# master.net
KiCad netlist of a schematic drawn in EAGLE
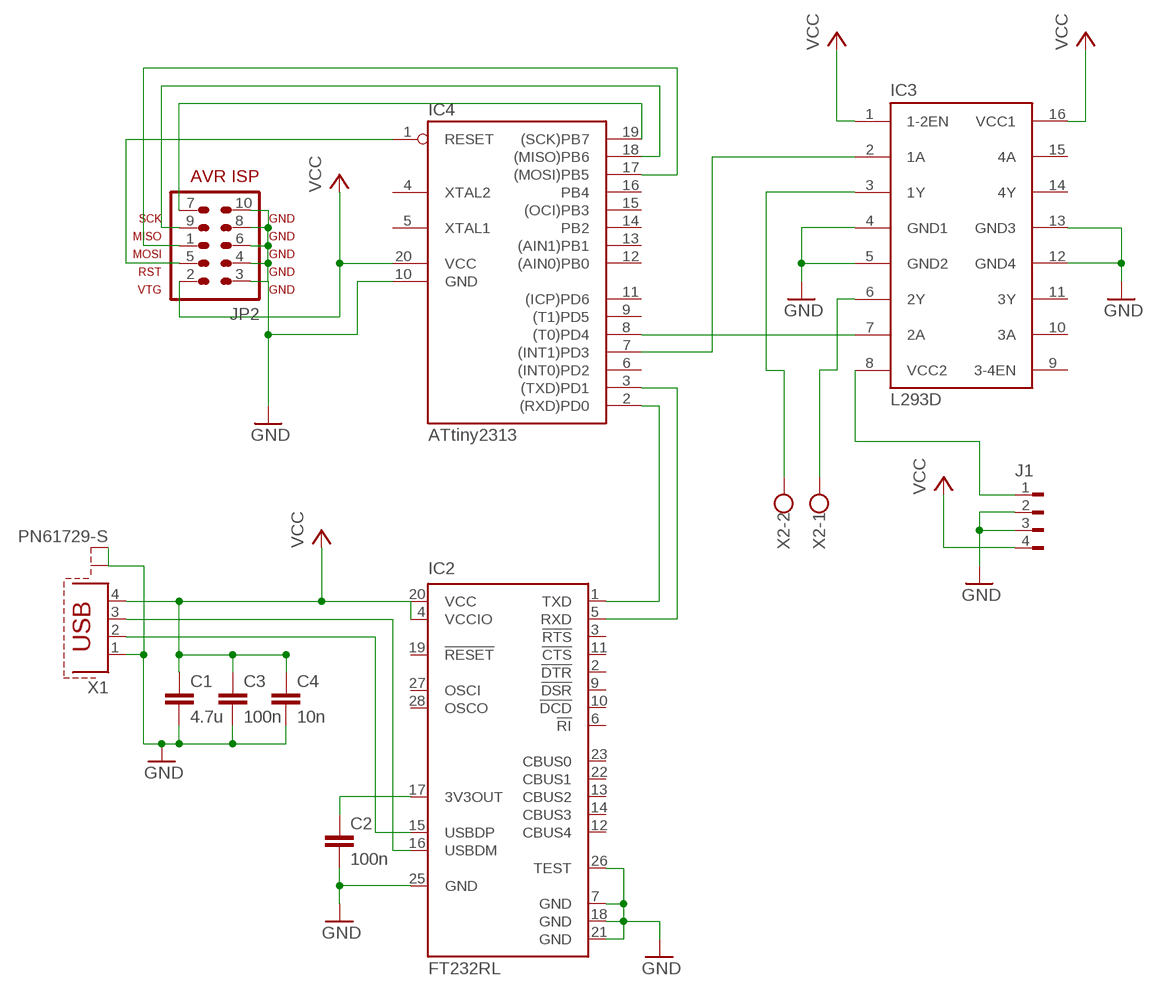
[diagram p0: schematic, sheet 1]

(export (version "E")
  (design (tool "Eeschema 10.0.6"))
  (components
    (comp (ref "C1")
      (value "4.7u")
      (footprint "eagle-import:C025-025X050")
      (libsource (lib "eagle-import") (part "C-EU025-025X050"))
    )
    (comp (ref "C2")
      (value "100n")
      (footprint "eagle-import:C025-025X050")
      (libsource (lib "eagle-import") (part "C-EU025-025X050"))
    )
    (comp (ref "C3")
      (value "100n")
      (footprint "eagle-import:C025-025X050")
      (libsource (lib "eagle-import") (part "C-EU025-025X050"))
    )
    (comp (ref "C4")
      (value "10n")
      (footprint "eagle-import:C025-025X050")
      (libsource (lib "eagle-import") (part "C-EU025-025X050"))
    )
    (comp (ref "IC2")
      (value "FT232RL")
      (footprint "eagle-import:SSOP28")
      (libsource (lib "eagle-import") (part "FT232RL"))
    )
    (comp (ref "IC3")
      (value "L293D")
      (footprint "eagle-import:DIL16")
      (libsource (lib "eagle-import") (part "L293D"))
    )
    (comp (ref "IC4")
      (value "ATtiny2313")
      (footprint "eagle-import:SO20L")
      (libsource (lib "eagle-import") (part "AT90S2313S"))
    )
    (comp (ref "J1")
      (value "FLOPPY-4")
      (footprint "eagle-import:FLOPPY-4")
      (libsource (lib "eagle-import") (part "FLOPPY-4"))
    )
    (comp (ref "JP2")
      (value "AVR-ISP-10")
      (footprint "eagle-import:AVR-ISP-10")
      (libsource (lib "eagle-import") (part "AVR-ISP-10"))
    )
    (comp (ref "X1")
      (value "PN61729-S")
      (footprint "eagle-import:PN61729-S")
      (libsource (lib "eagle-import") (part "PN61729-S"))
    )
    (comp (ref "X2")
      (value "W237-102")
      (footprint "eagle-import:W237-102")
      (fields (field (name "MPN") "237-102"))
      (libsource (lib "eagle-import") (part "W237-102"))
    )
  )
  (nets
    (net (code "1") (name "GND") (class "Default")
      (node (ref "C1") (pin "2") (pinfunction "2_2") (pintype "passive"))
      (node (ref "C2") (pin "2") (pinfunction "2_2") (pintype "passive"))
      (node (ref "C3") (pin "2") (pinfunction "2_2") (pintype "passive"))
      (node (ref "C4") (pin "2") (pinfunction "2_2") (pintype "passive"))
      (node (ref "IC2") (pin "18") (pinfunction "GND_18") (pintype "power_in"))
      (node (ref "IC2") (pin "21") (pinfunction "GND_21") (pintype "power_in"))
      (node (ref "IC2") (pin "25") (pinfunction "GND_25") (pintype "power_in"))
      (node (ref "IC2") (pin "26") (pinfunction "TEST_26") (pintype "input"))
      (node (ref "IC2") (pin "7") (pinfunction "GND_7") (pintype "power_in"))
      (node (ref "IC3") (pin "12") (pinfunction "GND4_12") (pintype "power_in"))
      (node (ref "IC3") (pin "13") (pinfunction "GND3_13") (pintype "power_in"))
      (node (ref "IC3") (pin "4") (pinfunction "GND1_4") (pintype "power_in"))
      (node (ref "IC3") (pin "5") (pinfunction "GND2_5") (pintype "power_in"))
      (node (ref "IC4") (pin "10") (pinfunction "GND_10") (pintype "power_in"))
      (node (ref "J1") (pin "2") (pinfunction "2_2") (pintype "passive"))
      (node (ref "J1") (pin "3") (pinfunction "3_3") (pintype "passive"))
      (node (ref "JP2") (pin "10") (pinfunction "10_10") (pintype "passive"))
      (node (ref "JP2") (pin "3") (pinfunction "3_3") (pintype "passive"))
      (node (ref "JP2") (pin "4") (pinfunction "4_4") (pintype "passive"))
      (node (ref "JP2") (pin "6") (pinfunction "6_6") (pintype "passive"))
      (node (ref "JP2") (pin "8") (pinfunction "8_8") (pintype "passive"))
      (node (ref "X1") (pin "1") (pinfunction "1_1") (pintype "passive"))
      (node (ref "X1") (pin "S1") (pinfunction "S1_S1") (pintype "passive"))
      (node (ref "X1") (pin "S2") (pinfunction "S2_S2") (pintype "passive"))
    )
    (net (code "2") (name "Net-(IC2-3V3OUT)") (class "Default")
      (node (ref "C2") (pin "1") (pinfunction "1_1") (pintype "passive"))
      (node (ref "IC2") (pin "17") (pinfunction "3V3OUT_17") (pintype "output"))
    )
    (net (code "3") (name "Net-(IC2-RXD)") (class "Default")
      (node (ref "IC2") (pin "5") (pinfunction "RXD_5") (pintype "input"))
      (node (ref "IC4") (pin "3") (pinfunction "(TXD)PD1_3") (pintype "bidirectional"))
    )
    (net (code "4") (name "Net-(IC2-TXD)") (class "Default")
      (node (ref "IC2") (pin "1") (pinfunction "TXD_1") (pintype "output"))
      (node (ref "IC4") (pin "2") (pinfunction "(RXD)PD0_2") (pintype "bidirectional"))
    )
    (net (code "5") (name "Net-(IC2-USBDM)") (class "Default")
      (node (ref "IC2") (pin "16") (pinfunction "USBDM_16") (pintype "bidirectional"))
      (node (ref "X1") (pin "3") (pinfunction "3_3") (pintype "passive"))
    )
    (net (code "6") (name "Net-(IC2-USBDP)") (class "Default")
      (node (ref "IC2") (pin "15") (pinfunction "USBDP_15") (pintype "bidirectional"))
      (node (ref "X1") (pin "2") (pinfunction "2_2") (pintype "passive"))
    )
    (net (code "7") (name "Net-(IC3-1A)") (class "Default")
      (node (ref "IC3") (pin "2") (pinfunction "1A_2") (pintype "input"))
      (node (ref "IC4") (pin "7") (pinfunction "(INT1)PD3_7") (pintype "bidirectional"))
    )
    (net (code "8") (name "Net-(IC3-1Y)") (class "Default")
      (node (ref "IC3") (pin "3") (pinfunction "1Y_3") (pintype "output"))
      (node (ref "X2") (pin "2") (pinfunction "KL_2") (pintype "passive"))
    )
    (net (code "9") (name "Net-(IC3-2A)") (class "Default")
      (node (ref "IC3") (pin "7") (pinfunction "2A_7") (pintype "input"))
      (node (ref "IC4") (pin "8") (pinfunction "(T0)PD4_8") (pintype "bidirectional"))
    )
    (net (code "10") (name "Net-(IC3-2Y)") (class "Default")
      (node (ref "IC3") (pin "6") (pinfunction "2Y_6") (pintype "output"))
      (node (ref "X2") (pin "1") (pinfunction "KL_1") (pintype "passive"))
    )
    (net (code "11") (name "Net-(IC3-VCC2)") (class "Default")
      (node (ref "IC3") (pin "8") (pinfunction "VCC2_8") (pintype "power_in"))
      (node (ref "J1") (pin "1") (pinfunction "1_1") (pintype "passive"))
    )
    (net (code "12") (name "Net-(IC4-(MISO)PB6)") (class "Default")
      (node (ref "IC4") (pin "18") (pinfunction "(MISO)PB6_18") (pintype "bidirectional"))
      (node (ref "JP2") (pin "9") (pinfunction "9_9") (pintype "passive"))
    )
    (net (code "13") (name "Net-(IC4-(MOSI)PB5)") (class "Default")
      (node (ref "IC4") (pin "17") (pinfunction "(MOSI)PB5_17") (pintype "bidirectional"))
      (node (ref "JP2") (pin "1") (pinfunction "1_1") (pintype "passive"))
    )
    (net (code "14") (name "Net-(IC4-(SCK)PB7)") (class "Default")
      (node (ref "IC4") (pin "19") (pinfunction "(SCK)PB7_19") (pintype "bidirectional"))
      (node (ref "JP2") (pin "7") (pinfunction "7_7") (pintype "passive"))
    )
    (net (code "15") (name "Net-(IC4-RESET)") (class "Default")
      (node (ref "IC4") (pin "1") (pinfunction "RESET_1") (pintype "bidirectional"))
      (node (ref "JP2") (pin "5") (pinfunction "5_5") (pintype "passive"))
    )
    (net (code "16") (name "VCC") (class "Default")
      (node (ref "C1") (pin "1") (pinfunction "1_1") (pintype "passive"))
      (node (ref "C3") (pin "1") (pinfunction "1_1") (pintype "passive"))
      (node (ref "C4") (pin "1") (pinfunction "1_1") (pintype "passive"))
      (node (ref "IC2") (pin "20") (pinfunction "VCC_20") (pintype "power_in"))
      (node (ref "IC2") (pin "4") (pinfunction "VCCIO_4") (pintype "power_in"))
      (node (ref "IC3") (pin "1") (pinfunction "1-2EN_1") (pintype "input"))
      (node (ref "IC3") (pin "16") (pinfunction "VCC1_16") (pintype "power_in"))
      (node (ref "IC4") (pin "20") (pinfunction "VCC_20") (pintype "power_in"))
      (node (ref "J1") (pin "4") (pinfunction "4_4") (pintype "passive"))
      (node (ref "JP2") (pin "2") (pinfunction "2_2") (pintype "passive"))
      (node (ref "X1") (pin "4") (pinfunction "4_4") (pintype "passive"))
    )
    (net (code "17") (name "unconnected-(IC2-CBUS0-Pad23)") (class "Default")
      (node (ref "IC2") (pin "23") (pinfunction "CBUS0_23") (pintype "bidirectional"))
    )
    (net (code "18") (name "unconnected-(IC2-CBUS1-Pad22)") (class "Default")
      (node (ref "IC2") (pin "22") (pinfunction "CBUS1_22") (pintype "bidirectional"))
    )
    (net (code "19") (name "unconnected-(IC2-CBUS2-Pad13)") (class "Default")
      (node (ref "IC2") (pin "13") (pinfunction "CBUS2_13") (pintype "bidirectional"))
    )
    (net (code "20") (name "unconnected-(IC2-CBUS3-Pad14)") (class "Default")
      (node (ref "IC2") (pin "14") (pinfunction "CBUS3_14") (pintype "bidirectional"))
    )
    (net (code "21") (name "unconnected-(IC2-CBUS4-Pad12)") (class "Default")
      (node (ref "IC2") (pin "12") (pinfunction "CBUS4_12") (pintype "bidirectional"))
    )
    (net (code "22") (name "unconnected-(IC2-OSCI-Pad27)") (class "Default")
      (node (ref "IC2") (pin "27") (pinfunction "OSCI_27") (pintype "input"))
    )
    (net (code "23") (name "unconnected-(IC2-OSCO-Pad28)") (class "Default")
      (node (ref "IC2") (pin "28") (pinfunction "OSCO_28") (pintype "output"))
    )
    (net (code "24") (name "unconnected-(IC2-~{CTS}-Pad11)") (class "Default")
      (node (ref "IC2") (pin "11") (pinfunction "~{CTS}_11") (pintype "input"))
    )
    (net (code "25") (name "unconnected-(IC2-~{DCD}-Pad10)") (class "Default")
      (node (ref "IC2") (pin "10") (pinfunction "~{DCD}_10") (pintype "input"))
    )
    (net (code "26") (name "unconnected-(IC2-~{DSR}-Pad9)") (class "Default")
      (node (ref "IC2") (pin "9") (pinfunction "~{DSR}_9") (pintype "input"))
    )
    (net (code "27") (name "unconnected-(IC2-~{DTR}-Pad2)") (class "Default")
      (node (ref "IC2") (pin "2") (pinfunction "~{DTR}_2") (pintype "output"))
    )
    (net (code "28") (name "unconnected-(IC2-~{RESET}-Pad19)") (class "Default")
      (node (ref "IC2") (pin "19") (pinfunction "~{RESET}_19") (pintype "input"))
    )
    (net (code "29") (name "unconnected-(IC2-~{RI}-Pad6)") (class "Default")
      (node (ref "IC2") (pin "6") (pinfunction "~{RI}_6") (pintype "input"))
    )
    (net (code "30") (name "unconnected-(IC2-~{RTS}-Pad3)") (class "Default")
      (node (ref "IC2") (pin "3") (pinfunction "~{RTS}_3") (pintype "output"))
    )
    (net (code "31") (name "unconnected-(IC3-3-4EN-Pad9)") (class "Default")
      (node (ref "IC3") (pin "9") (pinfunction "3-4EN_9") (pintype "input"))
    )
    (net (code "32") (name "unconnected-(IC3-3A-Pad10)") (class "Default")
      (node (ref "IC3") (pin "10") (pinfunction "3A_10") (pintype "input"))
    )
    (net (code "33") (name "unconnected-(IC3-3Y-Pad11)") (class "Default")
      (node (ref "IC3") (pin "11") (pinfunction "3Y_11") (pintype "output"))
    )
    (net (code "34") (name "unconnected-(IC3-4A-Pad15)") (class "Default")
      (node (ref "IC3") (pin "15") (pinfunction "4A_15") (pintype "input"))
    )
    (net (code "35") (name "unconnected-(IC3-4Y-Pad14)") (class "Default")
      (node (ref "IC3") (pin "14") (pinfunction "4Y_14") (pintype "output"))
    )
    (net (code "36") (name "unconnected-(IC4-(AIN0)PB0-Pad12)") (class "Default")
      (node (ref "IC4") (pin "12") (pinfunction "(AIN0)PB0_12") (pintype "bidirectional"))
    )
    (net (code "37") (name "unconnected-(IC4-(AIN1)PB1-Pad13)") (class "Default")
      (node (ref "IC4") (pin "13") (pinfunction "(AIN1)PB1_13") (pintype "bidirectional"))
    )
    (net (code "38") (name "unconnected-(IC4-(ICP)PD6-Pad11)") (class "Default")
      (node (ref "IC4") (pin "11") (pinfunction "(ICP)PD6_11") (pintype "bidirectional"))
    )
    (net (code "39") (name "unconnected-(IC4-(INT0)PD2-Pad6)") (class "Default")
      (node (ref "IC4") (pin "6") (pinfunction "(INT0)PD2_6") (pintype "bidirectional"))
    )
    (net (code "40") (name "unconnected-(IC4-(OCI)PB3-Pad15)") (class "Default")
      (node (ref "IC4") (pin "15") (pinfunction "(OCI)PB3_15") (pintype "bidirectional"))
    )
    (net (code "41") (name "unconnected-(IC4-(T1)PD5-Pad9)") (class "Default")
      (node (ref "IC4") (pin "9") (pinfunction "(T1)PD5_9") (pintype "bidirectional"))
    )
    (net (code "42") (name "unconnected-(IC4-PB2-Pad14)") (class "Default")
      (node (ref "IC4") (pin "14") (pinfunction "PB2_14") (pintype "bidirectional"))
    )
    (net (code "43") (name "unconnected-(IC4-PB4-Pad16)") (class "Default")
      (node (ref "IC4") (pin "16") (pinfunction "PB4_16") (pintype "bidirectional"))
    )
    (net (code "44") (name "unconnected-(IC4-XTAL1-Pad5)") (class "Default")
      (node (ref "IC4") (pin "5") (pinfunction "XTAL1_5") (pintype "bidirectional"))
    )
    (net (code "45") (name "unconnected-(IC4-XTAL2-Pad4)") (class "Default")
      (node (ref "IC4") (pin "4") (pinfunction "XTAL2_4") (pintype "bidirectional"))
    )
  )
)
